# RasPi_plate.net
KiCad netlist of a schematic drawn in EAGLE
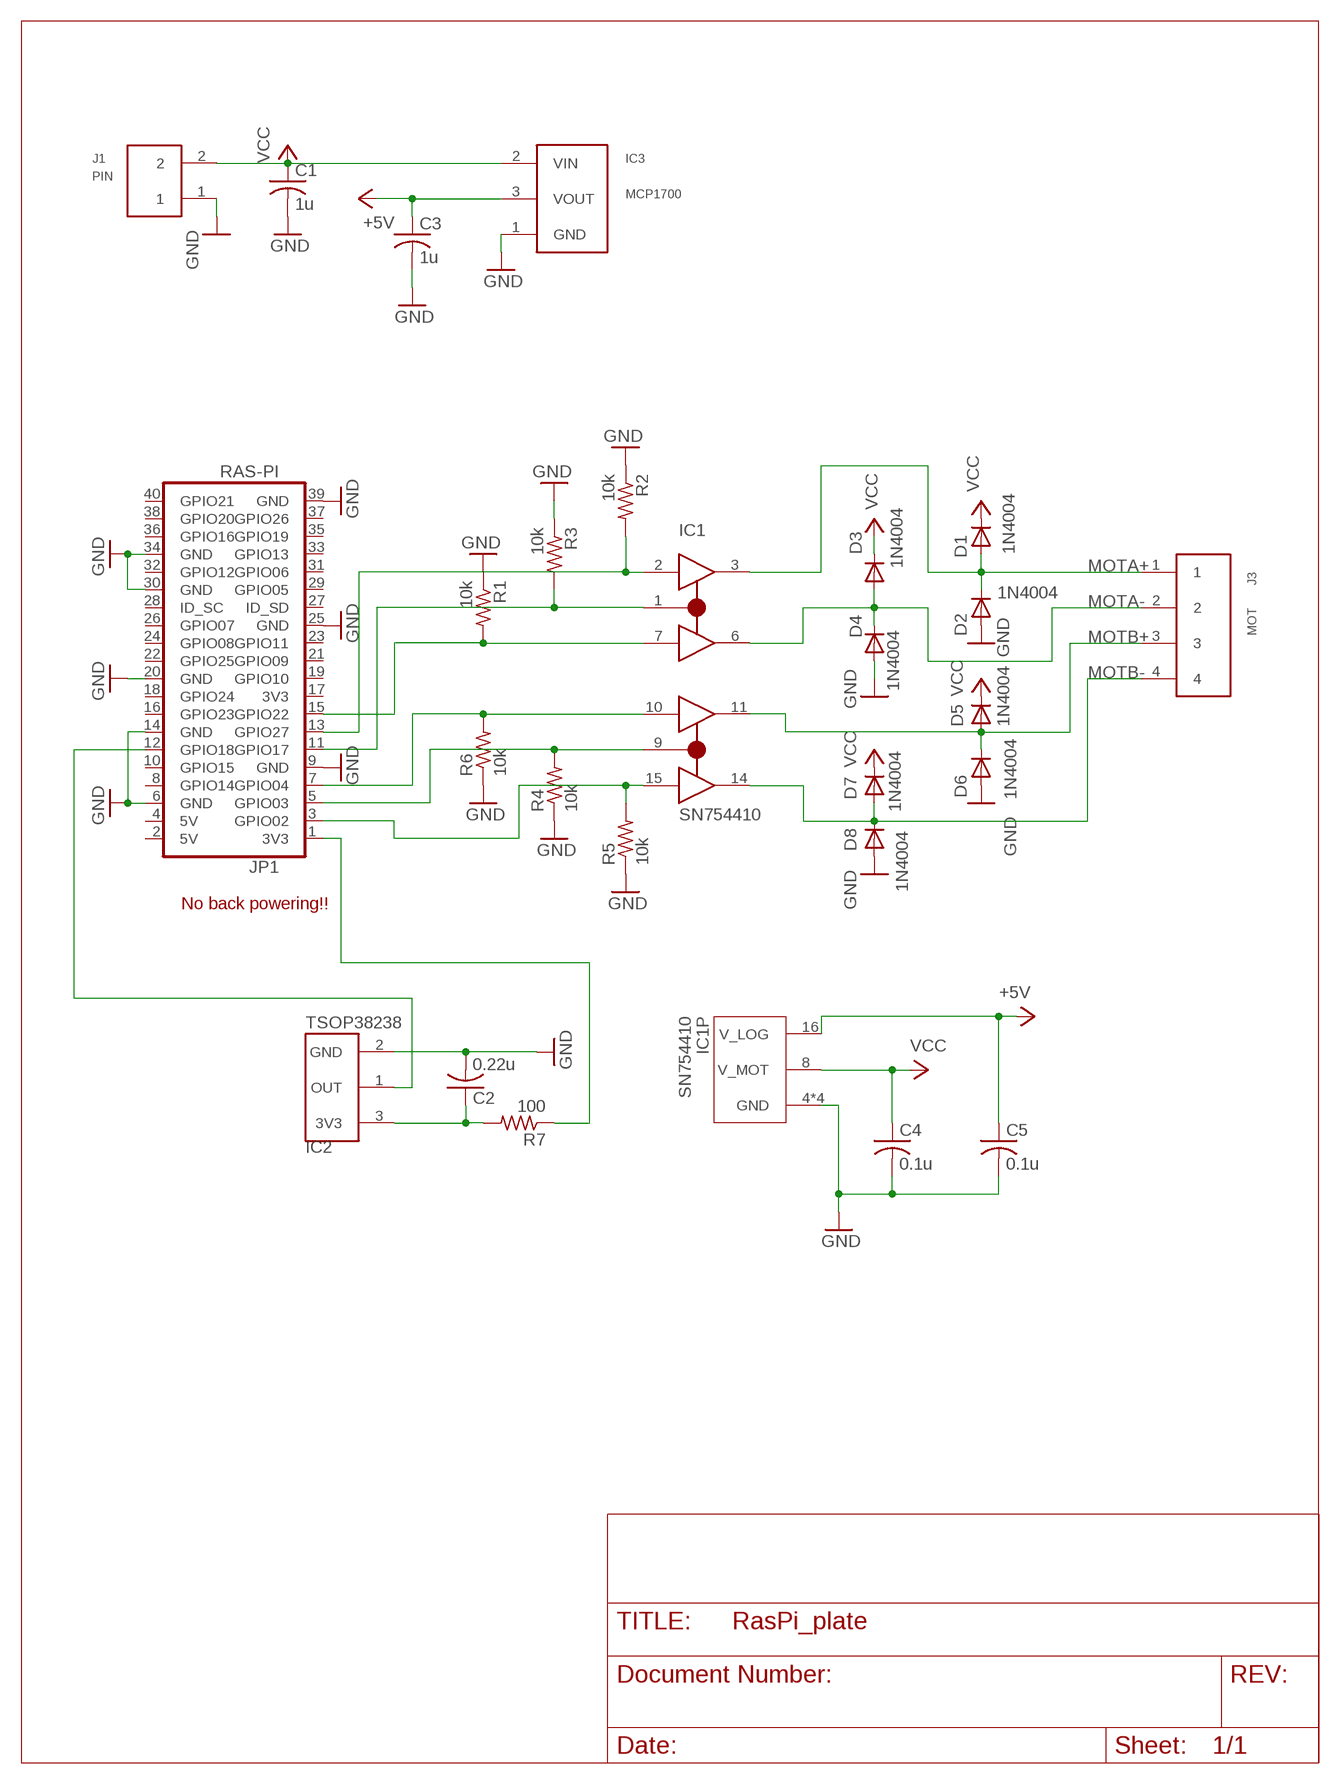
[diagram p0: schematic, sheet 1]

(export (version "E")
  (design (tool "Eeschema 10.0.6"))
  (components
    (comp (ref "C1")
      (value "1u")
      (footprint "eagle-import:C0805")
      (fields (field (name "MPN") "EMK212B7105KD-T"))
      (libsource (lib "eagle-import") (part "C-USC0805"))
    )
    (comp (ref "C2")
      (value "0.22u")
      (footprint "eagle-import:C0805")
      (fields (field (name "MPN") "MC0805B224M250CT"))
      (libsource (lib "eagle-import") (part "C-USC0805"))
    )
    (comp (ref "C3")
      (value "1u")
      (footprint "eagle-import:C0805")
      (fields (field (name "MPN") "EMK212B7105KD-T"))
      (libsource (lib "eagle-import") (part "C-USC0805"))
    )
    (comp (ref "C4")
      (value "0.1u")
      (footprint "eagle-import:C0805")
      (fields (field (name "MPN") "C2012X7R1H104K085AA"))
      (libsource (lib "eagle-import") (part "C-USC0805"))
    )
    (comp (ref "C5")
      (value "0.1u")
      (footprint "eagle-import:C0805")
      (fields (field (name "MPN") "C2012X7R1H104K085AA"))
      (libsource (lib "eagle-import") (part "C-USC0805"))
    )
    (comp (ref "D1")
      (value "1N4004")
      (footprint "eagle-import:DO41-10")
      (fields (field (name "MPN") "1N4007-E3/54"))
      (libsource (lib "eagle-import") (part "1N4004"))
    )
    (comp (ref "D2")
      (value "1N4004")
      (footprint "eagle-import:DO41-10")
      (fields (field (name "MPN") "1N4007-E3/54"))
      (libsource (lib "eagle-import") (part "1N4004"))
    )
    (comp (ref "D3")
      (value "1N4004")
      (footprint "eagle-import:DO41-10")
      (fields (field (name "MPN") "1N4007-E3/54"))
      (libsource (lib "eagle-import") (part "1N4004"))
    )
    (comp (ref "D4")
      (value "1N4004")
      (footprint "eagle-import:DO41-10")
      (fields (field (name "MPN") "1N4007-E3/54"))
      (libsource (lib "eagle-import") (part "1N4004"))
    )
    (comp (ref "D5")
      (value "1N4004")
      (footprint "eagle-import:DO41-10")
      (fields (field (name "MPN") "1N4007-E3/54"))
      (libsource (lib "eagle-import") (part "1N4004"))
    )
    (comp (ref "D6")
      (value "1N4004")
      (footprint "eagle-import:DO41-10")
      (fields (field (name "MPN") "1N4007-E3/54"))
      (libsource (lib "eagle-import") (part "1N4004"))
    )
    (comp (ref "D7")
      (value "1N4004")
      (footprint "eagle-import:DO41-10")
      (fields (field (name "MPN") "1N4007-E3/54"))
      (libsource (lib "eagle-import") (part "1N4004"))
    )
    (comp (ref "D8")
      (value "1N4004")
      (footprint "eagle-import:DO41-10")
      (fields (field (name "MPN") "1N4007-E3/54"))
      (libsource (lib "eagle-import") (part "1N4004"))
    )
    (comp (ref "IC1")
      (value "SN754410")
      (footprint "eagle-import:DIL16")
      (fields
        (field (name "MF") "TEXAS INSTRUMENTS")
        (field (name "MPN") "SN754410NE")
        (field (name "OC_NEWARK") "08F8145")
      )
      (libsource (lib "eagle-import") (part "SN754410"))
    )
    (comp (ref "IC2")
      (value "TSOP38238")
      (footprint "eagle-import:TSOP38238")
      (libsource (lib "eagle-import") (part "TSOP38238"))
    )
    (comp (ref "IC3")
      (value "MCP1700")
      (footprint "eagle-import:TO92")
      (fields (field (name "MPN") "MCP1700-5002E/TO"))
      (libsource (lib "eagle-import") (part "MCP1700"))
    )
    (comp (ref "J1")
      (value "PIN")
      (footprint "eagle-import:2PINHEAD")
      (libsource (lib "eagle-import") (part "2PINHEADER"))
    )
    (comp (ref "J3")
      (value "MOT")
      (footprint "eagle-import:4PINHEAD")
      (libsource (lib "eagle-import") (part "4PINHEADER"))
    )
    (comp (ref "JP1")
      (value "RAS-PI")
      (footprint "eagle-import:2X20")
      (libsource (lib "eagle-import") (part "40W_PI_HAT_TPH"))
    )
    (comp (ref "R1")
      (value "10k")
      (footprint "eagle-import:R0805")
      (fields (field (name "MPN") "MCHP05W4F1002T5E"))
      (libsource (lib "eagle-import") (part "R-US_R0805"))
    )
    (comp (ref "R2")
      (value "10k")
      (footprint "eagle-import:R0805")
      (fields (field (name "MPN") "MCHP05W4F1002T5E"))
      (libsource (lib "eagle-import") (part "R-US_R0805"))
    )
    (comp (ref "R3")
      (value "10k")
      (footprint "eagle-import:R0805")
      (fields (field (name "MPN") "MCHP05W4F1002T5E"))
      (libsource (lib "eagle-import") (part "R-US_R0805"))
    )
    (comp (ref "R4")
      (value "10k")
      (footprint "eagle-import:R0805")
      (fields (field (name "MPN") "MCHP05W4F1002T5E"))
      (libsource (lib "eagle-import") (part "R-US_R0805"))
    )
    (comp (ref "R5")
      (value "10k")
      (footprint "eagle-import:R0805")
      (fields (field (name "MPN") "MCHP05W4F1002T5E"))
      (libsource (lib "eagle-import") (part "R-US_R0805"))
    )
    (comp (ref "R6")
      (value "10k")
      (footprint "eagle-import:R0805")
      (fields (field (name "MPN") "MCHP05W4F1002T5E"))
      (libsource (lib "eagle-import") (part "R-US_R0805"))
    )
    (comp (ref "R7")
      (value "100")
      (footprint "eagle-import:R0805")
      (fields (field (name "MPN") "MCHP05W4F1000T5E"))
      (libsource (lib "eagle-import") (part "R-US_R0805"))
    )
  )
  (nets
    (net (code "1") (name "+5V") (class "Default")
      (node (ref "C3") (pin "1") (pinfunction "1_1") (pintype "bidirectional"))
      (node (ref "C5") (pin "1") (pinfunction "1_1") (pintype "bidirectional"))
      (node (ref "IC1") (pin "16") (pinfunction "V_LOG_16") (pintype "power_in"))
      (node (ref "IC3") (pin "3") (pinfunction "VOUT_3") (pintype "power_in"))
    )
    (net (code "2") (name "/MOTA+") (class "Default")
      (node (ref "D1") (pin "A") (pinfunction "A_A") (pintype "bidirectional"))
      (node (ref "D2") (pin "C") (pinfunction "C_C") (pintype "bidirectional"))
      (node (ref "IC1") (pin "3") (pinfunction "1Y_3") (pintype "bidirectional"))
      (node (ref "J3") (pin "1") (pinfunction "1_1") (pintype "bidirectional"))
    )
    (net (code "3") (name "/MOTA-") (class "Default")
      (node (ref "D3") (pin "A") (pinfunction "A_A") (pintype "bidirectional"))
      (node (ref "D4") (pin "C") (pinfunction "C_C") (pintype "bidirectional"))
      (node (ref "IC1") (pin "6") (pinfunction "2Y_6") (pintype "bidirectional"))
      (node (ref "J3") (pin "2") (pinfunction "2_2") (pintype "bidirectional"))
    )
    (net (code "4") (name "/MOTB+") (class "Default")
      (node (ref "D5") (pin "A") (pinfunction "A_A") (pintype "bidirectional"))
      (node (ref "D6") (pin "C") (pinfunction "C_C") (pintype "bidirectional"))
      (node (ref "IC1") (pin "11") (pinfunction "3Y_11") (pintype "bidirectional"))
      (node (ref "J3") (pin "3") (pinfunction "3_3") (pintype "bidirectional"))
    )
    (net (code "5") (name "/MOTB-") (class "Default")
      (node (ref "D7") (pin "A") (pinfunction "A_A") (pintype "bidirectional"))
      (node (ref "D8") (pin "C") (pinfunction "C_C") (pintype "bidirectional"))
      (node (ref "IC1") (pin "14") (pinfunction "4Y_14") (pintype "bidirectional"))
      (node (ref "J3") (pin "4") (pinfunction "4_4") (pintype "bidirectional"))
    )
    (net (code "6") (name "GND") (class "Default")
      (node (ref "C1") (pin "2") (pinfunction "2_2") (pintype "bidirectional"))
      (node (ref "C2") (pin "2") (pinfunction "2_2") (pintype "bidirectional"))
      (node (ref "C3") (pin "2") (pinfunction "2_2") (pintype "bidirectional"))
      (node (ref "C4") (pin "2") (pinfunction "2_2") (pintype "bidirectional"))
      (node (ref "C5") (pin "2") (pinfunction "2_2") (pintype "bidirectional"))
      (node (ref "D2") (pin "A") (pinfunction "A_A") (pintype "bidirectional"))
      (node (ref "D4") (pin "A") (pinfunction "A_A") (pintype "bidirectional"))
      (node (ref "D6") (pin "A") (pinfunction "A_A") (pintype "bidirectional"))
      (node (ref "D8") (pin "A") (pinfunction "A_A") (pintype "bidirectional"))
      (node (ref "IC1") (pin "12") (pinfunction "GND_12") (pintype "power_in"))
      (node (ref "IC1") (pin "13") (pinfunction "GND_13") (pintype "power_in"))
      (node (ref "IC1") (pin "4") (pinfunction "GND_4") (pintype "power_in"))
      (node (ref "IC1") (pin "5") (pinfunction "GND_5") (pintype "power_in"))
      (node (ref "IC2") (pin "2") (pinfunction "GND_2") (pintype "power_in"))
      (node (ref "IC3") (pin "1") (pinfunction "GND_1") (pintype "power_in"))
      (node (ref "J1") (pin "1") (pinfunction "1_1") (pintype "bidirectional"))
      (node (ref "JP1") (pin "14") (pinfunction "GND_14") (pintype "passive"))
      (node (ref "JP1") (pin "20") (pinfunction "GND_20") (pintype "passive"))
      (node (ref "JP1") (pin "25") (pinfunction "GND_25") (pintype "passive"))
      (node (ref "JP1") (pin "30") (pinfunction "GND_30") (pintype "passive"))
      (node (ref "JP1") (pin "34") (pinfunction "GND_34") (pintype "passive"))
      (node (ref "JP1") (pin "39") (pinfunction "GND_39") (pintype "passive"))
      (node (ref "JP1") (pin "6") (pinfunction "GND_6") (pintype "passive"))
      (node (ref "JP1") (pin "9") (pinfunction "GND_9") (pintype "passive"))
      (node (ref "R1") (pin "1") (pinfunction "1_1") (pintype "bidirectional"))
      (node (ref "R2") (pin "1") (pinfunction "1_1") (pintype "bidirectional"))
      (node (ref "R3") (pin "1") (pinfunction "1_1") (pintype "bidirectional"))
      (node (ref "R4") (pin "1") (pinfunction "1_1") (pintype "bidirectional"))
      (node (ref "R5") (pin "1") (pinfunction "1_1") (pintype "bidirectional"))
      (node (ref "R6") (pin "1") (pinfunction "1_1") (pintype "bidirectional"))
    )
    (net (code "7") (name "Net-(IC1A-1,2EN)") (class "Default")
      (node (ref "IC1") (pin "1") (pinfunction "1,2EN_1") (pintype "bidirectional"))
      (node (ref "JP1") (pin "11") (pinfunction "GPIO17_11") (pintype "passive"))
      (node (ref "R3") (pin "2") (pinfunction "2_2") (pintype "bidirectional"))
    )
    (net (code "8") (name "Net-(IC1A-1A)") (class "Default")
      (node (ref "IC1") (pin "2") (pinfunction "1A_2") (pintype "bidirectional"))
      (node (ref "JP1") (pin "13") (pinfunction "GPIO27_13") (pintype "passive"))
      (node (ref "R2") (pin "2") (pinfunction "2_2") (pintype "bidirectional"))
    )
    (net (code "9") (name "Net-(IC1A-2A)") (class "Default")
      (node (ref "IC1") (pin "7") (pinfunction "2A_7") (pintype "bidirectional"))
      (node (ref "JP1") (pin "15") (pinfunction "GPIO22_15") (pintype "passive"))
      (node (ref "R1") (pin "2") (pinfunction "2_2") (pintype "bidirectional"))
    )
    (net (code "10") (name "Net-(IC1A-3,4EN)") (class "Default")
      (node (ref "IC1") (pin "9") (pinfunction "3,4EN_9") (pintype "bidirectional"))
      (node (ref "JP1") (pin "5") (pinfunction "GPIO03_5") (pintype "passive"))
      (node (ref "R4") (pin "2") (pinfunction "2_2") (pintype "bidirectional"))
    )
    (net (code "11") (name "Net-(IC1A-3A)") (class "Default")
      (node (ref "IC1") (pin "10") (pinfunction "3A_10") (pintype "bidirectional"))
      (node (ref "JP1") (pin "7") (pinfunction "GPIO04_7") (pintype "passive"))
      (node (ref "R6") (pin "2") (pinfunction "2_2") (pintype "bidirectional"))
    )
    (net (code "12") (name "Net-(IC1A-4A)") (class "Default")
      (node (ref "IC1") (pin "15") (pinfunction "4A_15") (pintype "bidirectional"))
      (node (ref "JP1") (pin "3") (pinfunction "GPIO02_3") (pintype "passive"))
      (node (ref "R5") (pin "2") (pinfunction "2_2") (pintype "bidirectional"))
    )
    (net (code "13") (name "Net-(IC2-3V3)") (class "Default")
      (node (ref "C2") (pin "1") (pinfunction "1_1") (pintype "bidirectional"))
      (node (ref "IC2") (pin "3") (pinfunction "3V3_3") (pintype "power_in"))
      (node (ref "R7") (pin "2") (pinfunction "2_2") (pintype "bidirectional"))
    )
    (net (code "14") (name "Net-(IC2-OUT)") (class "Default")
      (node (ref "IC2") (pin "1") (pinfunction "OUT_1") (pintype "bidirectional"))
      (node (ref "JP1") (pin "12") (pinfunction "GPIO18_12") (pintype "passive"))
    )
    (net (code "15") (name "Net-(JP1-3V3-Pad1)") (class "Default")
      (node (ref "JP1") (pin "1") (pinfunction "3V3_1") (pintype "passive"))
      (node (ref "R7") (pin "1") (pinfunction "1_1") (pintype "bidirectional"))
    )
    (net (code "16") (name "VCC") (class "Default")
      (node (ref "C1") (pin "1") (pinfunction "1_1") (pintype "bidirectional"))
      (node (ref "C4") (pin "1") (pinfunction "1_1") (pintype "bidirectional"))
      (node (ref "D1") (pin "C") (pinfunction "C_C") (pintype "bidirectional"))
      (node (ref "D3") (pin "C") (pinfunction "C_C") (pintype "bidirectional"))
      (node (ref "D5") (pin "C") (pinfunction "C_C") (pintype "bidirectional"))
      (node (ref "D7") (pin "C") (pinfunction "C_C") (pintype "bidirectional"))
      (node (ref "IC1") (pin "8") (pinfunction "V_MOT_8") (pintype "power_in"))
      (node (ref "IC3") (pin "2") (pinfunction "VIN_2") (pintype "power_in"))
      (node (ref "J1") (pin "2") (pinfunction "2_2") (pintype "bidirectional"))
    )
    (net (code "17") (name "unconnected-(JP1-3V3-Pad17)") (class "Default")
      (node (ref "JP1") (pin "17") (pinfunction "3V3_17") (pintype "passive"))
    )
    (net (code "18") (name "unconnected-(JP1-5V-Pad2)") (class "Default")
      (node (ref "JP1") (pin "2") (pinfunction "5V_2") (pintype "passive"))
    )
    (net (code "19") (name "unconnected-(JP1-5V-Pad4)") (class "Default")
      (node (ref "JP1") (pin "4") (pinfunction "5V_4") (pintype "passive"))
    )
    (net (code "20") (name "unconnected-(JP1-GPIO05-Pad29)") (class "Default")
      (node (ref "JP1") (pin "29") (pinfunction "GPIO05_29") (pintype "passive"))
    )
    (net (code "21") (name "unconnected-(JP1-GPIO06-Pad31)") (class "Default")
      (node (ref "JP1") (pin "31") (pinfunction "GPIO06_31") (pintype "passive"))
    )
    (net (code "22") (name "unconnected-(JP1-GPIO07-Pad26)") (class "Default")
      (node (ref "JP1") (pin "26") (pinfunction "GPIO07_26") (pintype "passive"))
    )
    (net (code "23") (name "unconnected-(JP1-GPIO08-Pad24)") (class "Default")
      (node (ref "JP1") (pin "24") (pinfunction "GPIO08_24") (pintype "passive"))
    )
    (net (code "24") (name "unconnected-(JP1-GPIO09-Pad21)") (class "Default")
      (node (ref "JP1") (pin "21") (pinfunction "GPIO09_21") (pintype "passive"))
    )
    (net (code "25") (name "unconnected-(JP1-GPIO10-Pad19)") (class "Default")
      (node (ref "JP1") (pin "19") (pinfunction "GPIO10_19") (pintype "passive"))
    )
    (net (code "26") (name "unconnected-(JP1-GPIO11-Pad23)") (class "Default")
      (node (ref "JP1") (pin "23") (pinfunction "GPIO11_23") (pintype "passive"))
    )
    (net (code "27") (name "unconnected-(JP1-GPIO12-Pad32)") (class "Default")
      (node (ref "JP1") (pin "32") (pinfunction "GPIO12_32") (pintype "passive"))
    )
    (net (code "28") (name "unconnected-(JP1-GPIO13-Pad33)") (class "Default")
      (node (ref "JP1") (pin "33") (pinfunction "GPIO13_33") (pintype "passive"))
    )
    (net (code "29") (name "unconnected-(JP1-GPIO14-Pad8)") (class "Default")
      (node (ref "JP1") (pin "8") (pinfunction "GPIO14_8") (pintype "passive"))
    )
    (net (code "30") (name "unconnected-(JP1-GPIO15-Pad10)") (class "Default")
      (node (ref "JP1") (pin "10") (pinfunction "GPIO15_10") (pintype "passive"))
    )
    (net (code "31") (name "unconnected-(JP1-GPIO16-Pad36)") (class "Default")
      (node (ref "JP1") (pin "36") (pinfunction "GPIO16_36") (pintype "passive"))
    )
    (net (code "32") (name "unconnected-(JP1-GPIO19-Pad35)") (class "Default")
      (node (ref "JP1") (pin "35") (pinfunction "GPIO19_35") (pintype "passive"))
    )
    (net (code "33") (name "unconnected-(JP1-GPIO20-Pad38)") (class "Default")
      (node (ref "JP1") (pin "38") (pinfunction "GPIO20_38") (pintype "passive"))
    )
    (net (code "34") (name "unconnected-(JP1-GPIO21-Pad40)") (class "Default")
      (node (ref "JP1") (pin "40") (pinfunction "GPIO21_40") (pintype "passive"))
    )
    (net (code "35") (name "unconnected-(JP1-GPIO23-Pad16)") (class "Default")
      (node (ref "JP1") (pin "16") (pinfunction "GPIO23_16") (pintype "passive"))
    )
    (net (code "36") (name "unconnected-(JP1-GPIO24-Pad18)") (class "Default")
      (node (ref "JP1") (pin "18") (pinfunction "GPIO24_18") (pintype "passive"))
    )
    (net (code "37") (name "unconnected-(JP1-GPIO25-Pad22)") (class "Default")
      (node (ref "JP1") (pin "22") (pinfunction "GPIO25_22") (pintype "passive"))
    )
    (net (code "38") (name "unconnected-(JP1-GPIO26-Pad37)") (class "Default")
      (node (ref "JP1") (pin "37") (pinfunction "GPIO26_37") (pintype "passive"))
    )
    (net (code "39") (name "unconnected-(JP1-ID_SC-Pad28)") (class "Default")
      (node (ref "JP1") (pin "28") (pinfunction "ID_SC_28") (pintype "passive"))
    )
    (net (code "40") (name "unconnected-(JP1-ID_SD-Pad27)") (class "Default")
      (node (ref "JP1") (pin "27") (pinfunction "ID_SD_27") (pintype "passive"))
    )
  )
)
